# p1_apfc_and_standby.net
KiCad netlist of a schematic drawn in Altium Designer
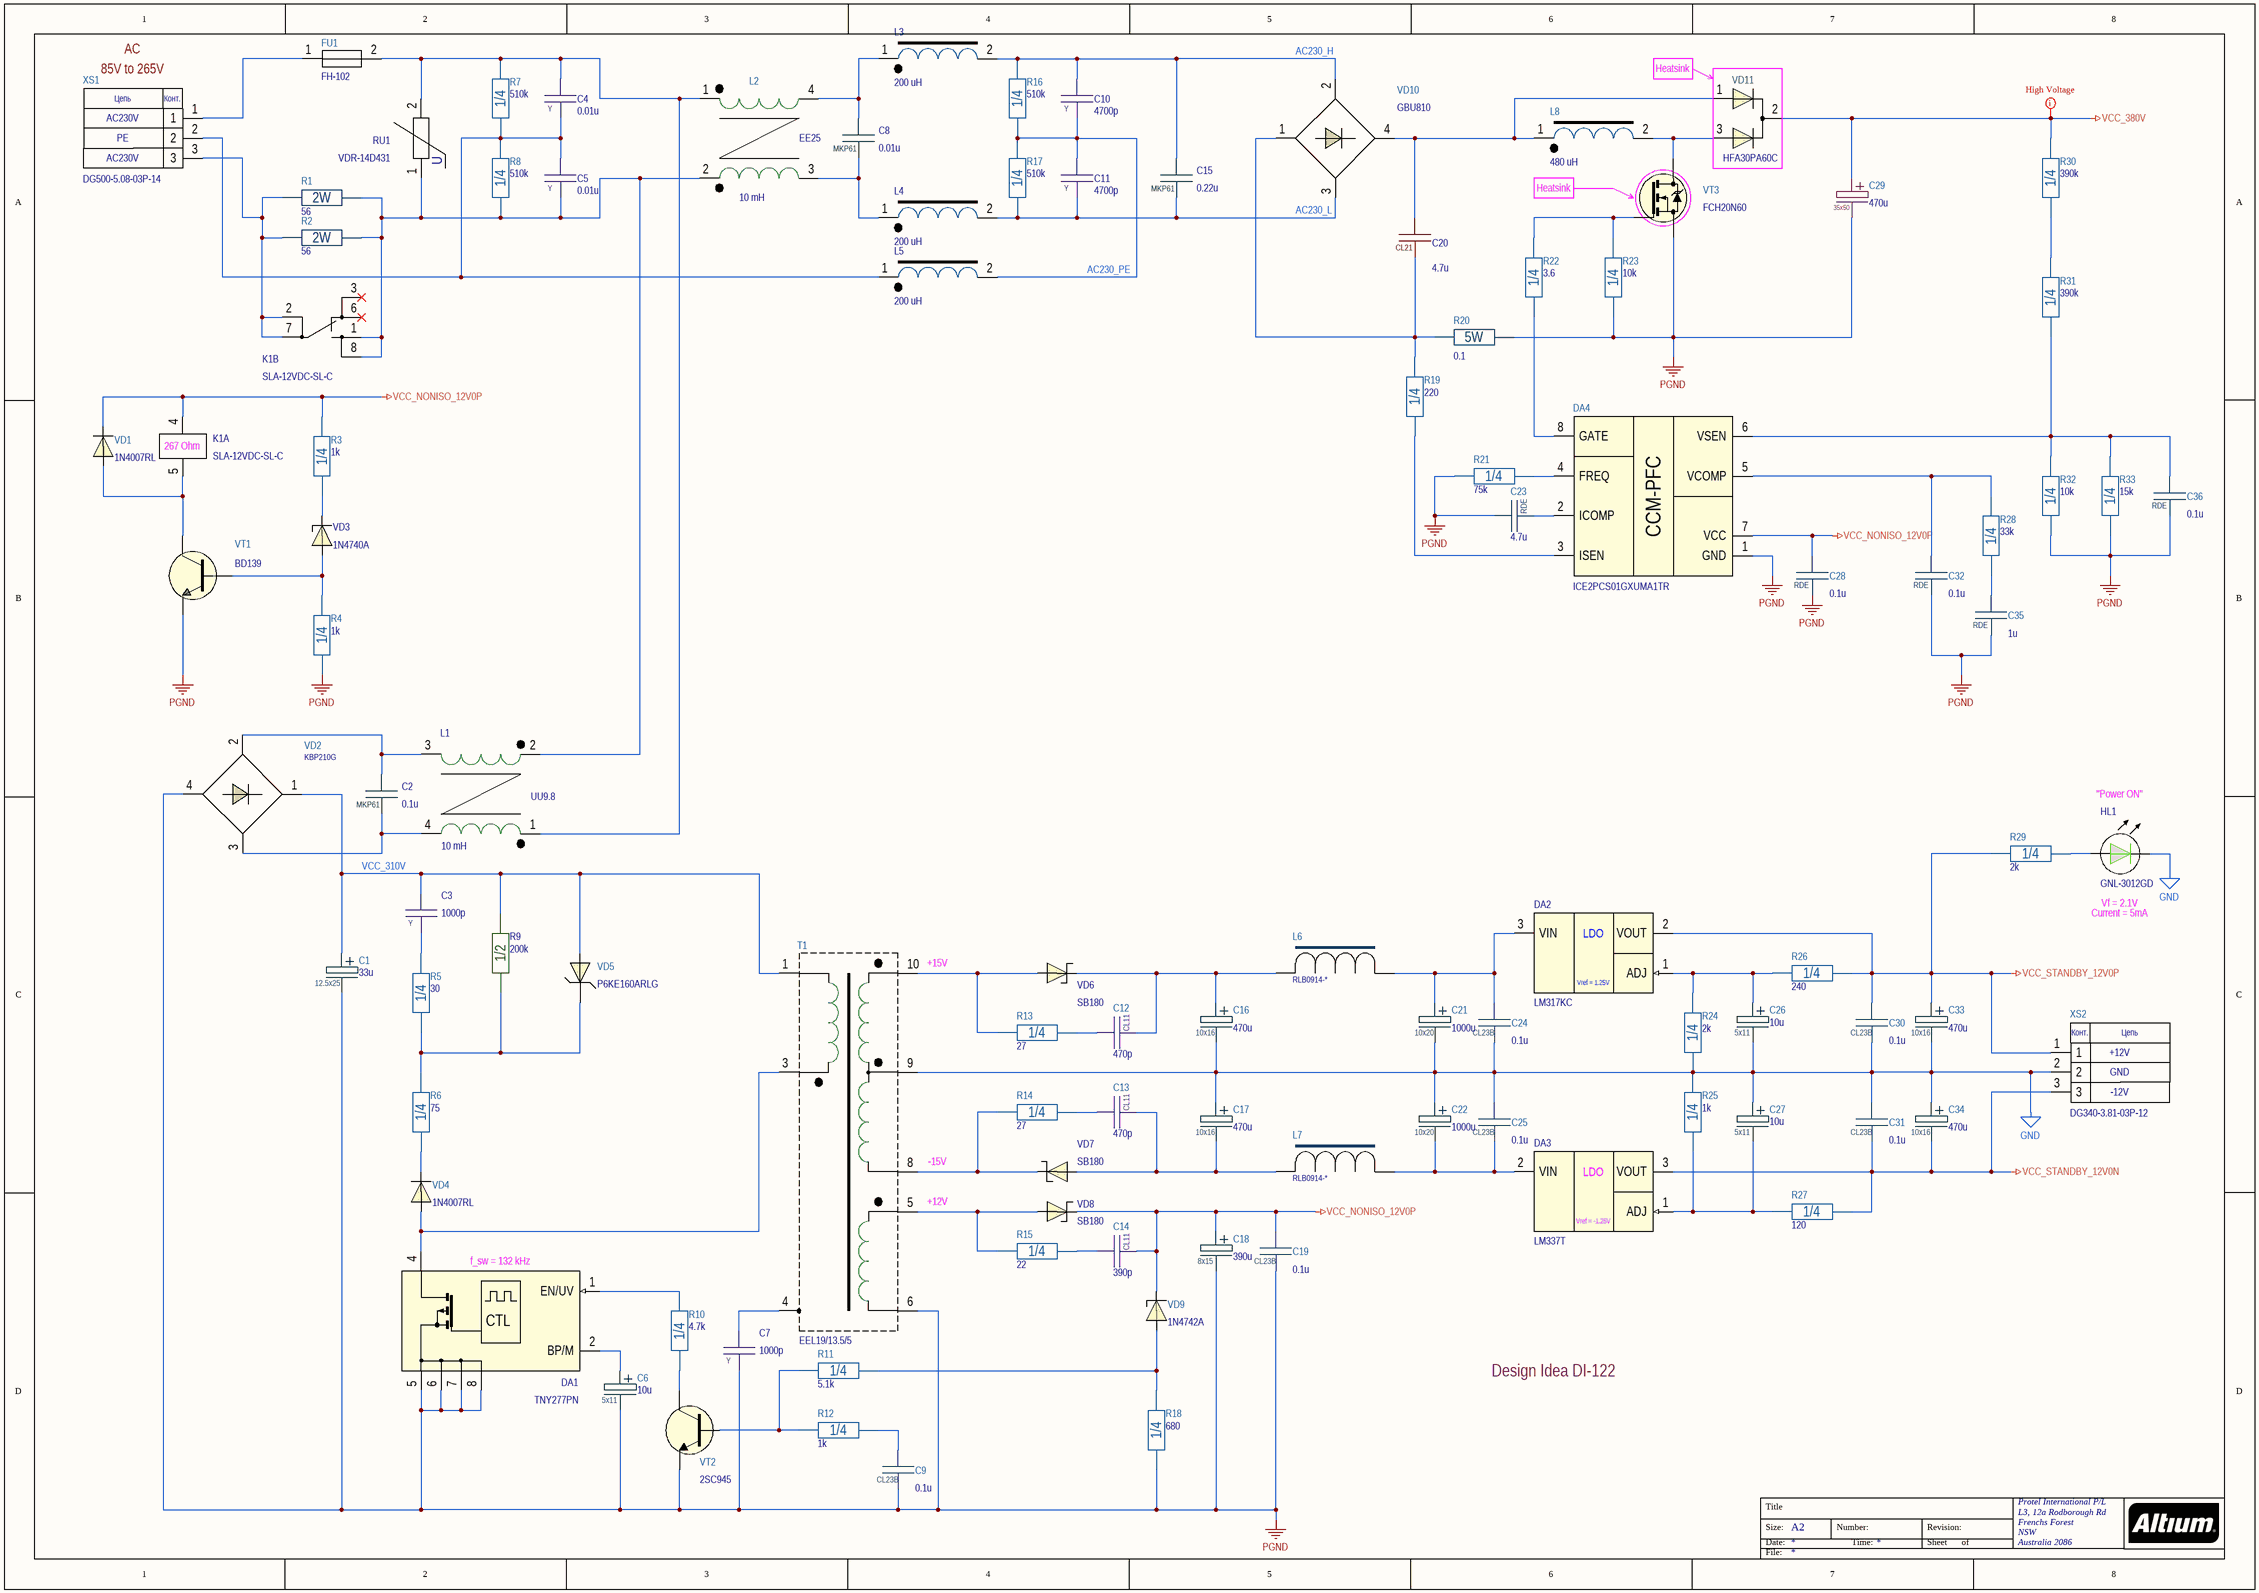
[diagram p0: p1_apfc_and_standby.SchDoc]

(export (version "E")
  (design (tool "Eeschema 10.0.6"))
  (components
    (comp (ref "C1")
      (value "33u")
      (footprint "PcbLib_RC:ECAP13X21X5_BRW")
      (description "Aluminium capacitor")
      (fields
        (field (name "TOLERANCE") "± 20 %")
        (field (name "VOLTAGE") "400V")
        (field (name "PACKAGE") "12.5x25")
      )
      (libsource (lib "Schlib_RC") (part "C_ECAP"))
    )
    (comp (ref "C2")
      (value "0.1u")
      (footprint "PcbLib_RC:MKP61_13x12x6_P10")
      (description "Metallized Polypropylene Film Capacitor for high voltage application")
      (fields
        (field (name "TOLERANCE") "± 10 %")
        (field (name "VOLTAGE") "300V")
        (field (name "PACKAGE") "MKP61")
      )
      (libsource (lib "Schlib_RC") (part "MKP61"))
    )
    (comp (ref "C3")
      (value "1000p")
      (footprint "PcbLib_RC:JYC_Y2_CAP_7.5")
      (description "High Voltage Ceramic Capacitor")
      (fields
        (field (name "TOLERANCE") "± 20 %")
        (field (name "VOLTAGE") "2000V")
        (field (name "PACKAGE") "Y")
      )
      (libsource (lib "Schlib_RC") (part "JB_Y2"))
    )
    (comp (ref "C4")
      (value "0.01u")
      (footprint "PcbLib_RC:JYC_Y2_CAP_6.5")
      (description "High Voltage Ceramic Capacitor")
      (fields
        (field (name "TOLERANCE") "± 20 %")
        (field (name "VOLTAGE") "2000V")
        (field (name "PACKAGE") "Y")
      )
      (libsource (lib "Schlib_RC") (part "JB_Y2"))
    )
    (comp (ref "C5")
      (value "0.01u")
      (footprint "PcbLib_RC:JYC_Y2_CAP_6.5")
      (description "High Voltage Ceramic Capacitor")
      (fields
        (field (name "TOLERANCE") "± 20 %")
        (field (name "VOLTAGE") "2000V")
        (field (name "PACKAGE") "Y")
      )
      (libsource (lib "Schlib_RC") (part "JB_Y2"))
    )
    (comp (ref "C6")
      (value "10u")
      (footprint "PcbLib_RC:ECAP5X11X2.0_BRW")
      (description "Aluminium capacitor")
      (fields
        (field (name "TOLERANCE") "± 20 %")
        (field (name "VOLTAGE") "63V")
        (field (name "PACKAGE") "5x11")
      )
      (libsource (lib "Schlib_RC") (part "C_ECAP"))
    )
    (comp (ref "C7")
      (value "1000p")
      (footprint "PcbLib_RC:JYC_Y2_CAP_7.5")
      (description "High Voltage Ceramic Capacitor")
      (fields
        (field (name "TOLERANCE") "± 20 %")
        (field (name "VOLTAGE") "2000V")
        (field (name "PACKAGE") "Y")
      )
      (libsource (lib "Schlib_RC") (part "JB_Y2"))
    )
    (comp (ref "C8")
      (value "0.01u")
      (footprint "PcbLib_RC:MKP61_18x12x6_P15")
      (description "Metallized Polypropylene Film Capacitor for high voltage application")
      (fields
        (field (name "TOLERANCE") "± 10 %")
        (field (name "VOLTAGE") "300V")
        (field (name "PACKAGE") "MKP61")
      )
      (libsource (lib "Schlib_RC") (part "MKP61"))
    )
    (comp (ref "C9")
      (value "0.1u")
      (footprint "PcbLib_RC:CL23B_7.2x2.5")
      (description "Box-type metallized polyester film capacitor")
      (fields
        (field (name "TOLERANCE") "± * %")
        (field (name "VOLTAGE") "63V")
        (field (name "PACKAGE") "CL23B")
      )
      (libsource (lib "Schlib_RC") (part "CL23B"))
    )
    (comp (ref "C10")
      (value "4700p")
      (footprint "PcbLib_RC:JYC_Y2_CAP_6.5")
      (description "High Voltage Ceramic Capacitor")
      (fields
        (field (name "TOLERANCE") "± 20 %")
        (field (name "VOLTAGE") "2000V")
        (field (name "PACKAGE") "Y")
      )
      (libsource (lib "Schlib_RC") (part "JB_Y2"))
    )
    (comp (ref "C11")
      (value "4700p")
      (footprint "PcbLib_RC:JYC_Y2_CAP_6.5")
      (description "High Voltage Ceramic Capacitor")
      (fields
        (field (name "TOLERANCE") "± 20 %")
        (field (name "VOLTAGE") "2000V")
        (field (name "PACKAGE") "Y")
      )
      (libsource (lib "Schlib_RC") (part "JB_Y2"))
    )
    (comp (ref "C12")
      (value "470p")
      (footprint "PcbLib_RC:CL11_6x4_P4.0")
      (description "CL11 Type Polyester Film Metal Foil Capacitor-inductive")
      (fields
        (field (name "TOLERANCE") "± 5 %")
        (field (name "VOLTAGE") "100V")
        (field (name "PACKAGE") "CL11")
      )
      (libsource (lib "Schlib_RC") (part "CL11"))
    )
    (comp (ref "C13")
      (value "470p")
      (footprint "PcbLib_RC:CL11_6x4_P4.0")
      (description "CL11 Type Polyester Film Metal Foil Capacitor-inductive")
      (fields
        (field (name "TOLERANCE") "± 5 %")
        (field (name "VOLTAGE") "100V")
        (field (name "PACKAGE") "CL11")
      )
      (libsource (lib "Schlib_RC") (part "CL11"))
    )
    (comp (ref "C14")
      (value "390p")
      (footprint "PcbLib_RC:CL11_6x4_P4.0")
      (description "CL11 Type Polyester Film Metal Foil Capacitor-inductive")
      (fields
        (field (name "TOLERANCE") "± 5 %")
        (field (name "VOLTAGE") "100V")
        (field (name "PACKAGE") "CL11")
      )
      (libsource (lib "Schlib_RC") (part "CL11"))
    )
    (comp (ref "C15")
      (value "0.22u")
      (footprint "PcbLib_RC:MKP61_18x14.5x8.5_P15")
      (description "Metallized Polypropylene Film Capacitor for high voltage application")
      (fields
        (field (name "TOLERANCE") "± 10 %")
        (field (name "VOLTAGE") "300V")
        (field (name "PACKAGE") "MKP61")
      )
      (libsource (lib "Schlib_RC") (part "MKP61"))
    )
    (comp (ref "C16")
      (value "470u")
      (footprint "PcbLib_RC:ECAP10X17X5_BRW")
      (description "Aluminium capacitor")
      (fields
        (field (name "TOLERANCE") "± 20 %")
        (field (name "VOLTAGE") "25V")
        (field (name "PACKAGE") "10x16")
      )
      (libsource (lib "Schlib_RC") (part "C_ECAP"))
    )
    (comp (ref "C17")
      (value "470u")
      (footprint "PcbLib_RC:ECAP10X17X5_BRW")
      (description "Aluminium capacitor")
      (fields
        (field (name "TOLERANCE") "± 20 %")
        (field (name "VOLTAGE") "25V")
        (field (name "PACKAGE") "10x16")
      )
      (libsource (lib "Schlib_RC") (part "C_ECAP"))
    )
    (comp (ref "C18")
      (value "390u")
      (footprint "PcbLib_RC:ECAP8X13.5X3.5_BRW")
      (description "Aluminium capacitor")
      (fields
        (field (name "TOLERANCE") "± 20 %")
        (field (name "VOLTAGE") "25V")
        (field (name "PACKAGE") "8x15")
      )
      (libsource (lib "Schlib_RC") (part "C_ECAP"))
    )
    (comp (ref "C19")
      (value "0.1u")
      (footprint "PcbLib_RC:CL23B_7.2x2.5")
      (description "Box-type metallized polyester film capacitor")
      (fields
        (field (name "TOLERANCE") "± * %")
        (field (name "VOLTAGE") "63V")
        (field (name "PACKAGE") "CL23B")
      )
      (libsource (lib "Schlib_RC") (part "CL23B"))
    )
    (comp (ref "C20")
      (value "4.7u")
      (footprint "PcbLib_RC:CL21_29x24.5x14.0_P27.5")
      (description "CL21 Type Metallized Polyester Film Capacitor")
      (fields
        (field (name "TOLERANCE") "± * %")
        (field (name "VOLTAGE") "630V")
        (field (name "PACKAGE") "CL21")
      )
      (libsource (lib "Schlib_RC") (part "CL21"))
    )
    (comp (ref "C21")
      (value "1000u")
      (footprint "PcbLib_RC:ECAP10X21X5_BRW")
      (description "Aluminium capacitor")
      (fields
        (field (name "TOLERANCE") "± 20 %")
        (field (name "VOLTAGE") "25V")
        (field (name "PACKAGE") "10x20")
      )
      (libsource (lib "Schlib_RC") (part "C_ECAP"))
    )
    (comp (ref "C22")
      (value "1000u")
      (footprint "PcbLib_RC:ECAP10X21X5_BRW")
      (description "Aluminium capacitor")
      (fields
        (field (name "TOLERANCE") "± 20 %")
        (field (name "VOLTAGE") "25V")
        (field (name "PACKAGE") "10x20")
      )
      (libsource (lib "Schlib_RC") (part "C_ECAP"))
    )
    (comp (ref "C23")
      (value "4.7u")
      (footprint "PcbLib_RC:RDE_2P1")
      (description "MLCC radial lead type with epoxy coat (RDE Series)")
      (fields
        (field (name "TOLERANCE") "± 10 %")
        (field (name "VOLTAGE") "50V")
        (field (name "PACKAGE") "RDE")
      )
      (libsource (lib "Schlib_RC") (part "RDE_CAP"))
    )
    (comp (ref "C24")
      (value "0.1u")
      (footprint "PcbLib_RC:CL23B_7.2x2.5")
      (description "Box-type metallized polyester film capacitor")
      (fields
        (field (name "TOLERANCE") "± * %")
        (field (name "VOLTAGE") "63V")
        (field (name "PACKAGE") "CL23B")
      )
      (libsource (lib "Schlib_RC") (part "CL23B"))
    )
    (comp (ref "C25")
      (value "0.1u")
      (footprint "PcbLib_RC:CL23B_7.2x2.5")
      (description "Box-type metallized polyester film capacitor")
      (fields
        (field (name "TOLERANCE") "± * %")
        (field (name "VOLTAGE") "63V")
        (field (name "PACKAGE") "CL23B")
      )
      (libsource (lib "Schlib_RC") (part "CL23B"))
    )
    (comp (ref "C26")
      (value "10u")
      (footprint "PcbLib_RC:ECAP5X11X2.0_BRW")
      (description "Aluminium capacitor")
      (fields
        (field (name "TOLERANCE") "± 20 %")
        (field (name "VOLTAGE") "63V")
        (field (name "PACKAGE") "5x11")
      )
      (libsource (lib "Schlib_RC") (part "C_ECAP"))
    )
    (comp (ref "C27")
      (value "10u")
      (footprint "PcbLib_RC:ECAP5X11X2.0_BRW")
      (description "Aluminium capacitor")
      (fields
        (field (name "TOLERANCE") "± 20 %")
        (field (name "VOLTAGE") "63V")
        (field (name "PACKAGE") "5x11")
      )
      (libsource (lib "Schlib_RC") (part "C_ECAP"))
    )
    (comp (ref "C28")
      (value "0.1u")
      (footprint "PcbLib_RC:RDE_1P1")
      (description "MLCC radial lead type with epoxy coat (RDE Series)")
      (fields
        (field (name "TOLERANCE") "± 10 %")
        (field (name "VOLTAGE") "100V")
        (field (name "PACKAGE") "RDE")
      )
      (libsource (lib "Schlib_RC") (part "RDE_CAP"))
    )
    (comp (ref "C29")
      (value "470u")
      (footprint "PcbLib_RC:ECAP35X50X10")
      (description "Aluminium capacitors 35x50mm")
      (fields
        (field (name "TOLERANCE") "± 20 %")
        (field (name "VOLTAGE") "450V")
        (field (name "PACKAGE") "35x50")
      )
      (libsource (lib "Schlib_RC") (part "ECAP_35x50"))
    )
    (comp (ref "C30")
      (value "0.1u")
      (footprint "PcbLib_RC:CL23B_7.2x2.5")
      (description "Box-type metallized polyester film capacitor")
      (fields
        (field (name "TOLERANCE") "± * %")
        (field (name "VOLTAGE") "63V")
        (field (name "PACKAGE") "CL23B")
      )
      (libsource (lib "Schlib_RC") (part "CL23B"))
    )
    (comp (ref "C31")
      (value "0.1u")
      (footprint "PcbLib_RC:CL23B_7.2x2.5")
      (description "Box-type metallized polyester film capacitor")
      (fields
        (field (name "TOLERANCE") "± * %")
        (field (name "VOLTAGE") "63V")
        (field (name "PACKAGE") "CL23B")
      )
      (libsource (lib "Schlib_RC") (part "CL23B"))
    )
    (comp (ref "C32")
      (value "0.1u")
      (footprint "PcbLib_RC:RDE_1P1")
      (description "MLCC radial lead type with epoxy coat (RDE Series)")
      (fields
        (field (name "TOLERANCE") "± 10 %")
        (field (name "VOLTAGE") "100V")
        (field (name "PACKAGE") "RDE")
      )
      (libsource (lib "Schlib_RC") (part "RDE_CAP"))
    )
    (comp (ref "C33")
      (value "470u")
      (footprint "PcbLib_RC:ECAP10X17X5_BRW")
      (description "Aluminium capacitor")
      (fields
        (field (name "TOLERANCE") "± 20 %")
        (field (name "VOLTAGE") "25V")
        (field (name "PACKAGE") "10x16")
      )
      (libsource (lib "Schlib_RC") (part "C_ECAP"))
    )
    (comp (ref "C34")
      (value "470u")
      (footprint "PcbLib_RC:ECAP10X17X5_BRW")
      (description "Aluminium capacitor")
      (fields
        (field (name "TOLERANCE") "± 20 %")
        (field (name "VOLTAGE") "25V")
        (field (name "PACKAGE") "10x16")
      )
      (libsource (lib "Schlib_RC") (part "C_ECAP"))
    )
    (comp (ref "C35")
      (value "1u")
      (footprint "PcbLib_RC:RDE_2P1")
      (description "MLCC radial lead type with epoxy coat (RDE Series)")
      (fields
        (field (name "TOLERANCE") "± 10 %")
        (field (name "VOLTAGE") "50V")
        (field (name "PACKAGE") "RDE")
      )
      (libsource (lib "Schlib_RC") (part "RDE_CAP"))
    )
    (comp (ref "C36")
      (value "0.1u")
      (footprint "PcbLib_RC:RDE_1P1")
      (description "MLCC radial lead type with epoxy coat (RDE Series)")
      (fields
        (field (name "TOLERANCE") "± 10 %")
        (field (name "VOLTAGE") "100V")
        (field (name "PACKAGE") "RDE")
      )
      (libsource (lib "Schlib_RC") (part "RDE_CAP"))
    )
    (comp (ref "DA1")
      (value "TNY277PN")
      (footprint "PcbLib_ICs:DIP-8C")
      (description "Energy-Effi cient, Off-Line Switcher With Enhanced Flexibility and Extended Power Range")
      (fields (field (name "MANUFACTURER") "Power Integrations"))
      (libsource (lib "Schlib_OtherComponents") (part "TNY277PN"))
    )
    (comp (ref "DA2")
      (value "LM317KC")
      (footprint "PcbLib_ICs:TO-220A-3")
      (description "1.5 A 3-Terminal Adjustable Regulator")
      (fields (field (name "MANUFACTURER") "Texas Instruments"))
      (libsource (lib "Schlib_Texas_Instruments") (part "LM317KC"))
    )
    (comp (ref "DA3")
      (value "LM337T")
      (footprint "PcbLib_ICs:TO-220A-3")
      (description "-1.5A  3-Terminal Adjustable Negative Regulators")
      (fields (field (name "MANUFACTURER") "Texas Instruments"))
      (libsource (lib "Schlib_Texas_Instruments") (part "LM337T"))
    )
    (comp (ref "DA4")
      (value "ICE2PCS01GXUMA1TR")
      (footprint "PcbLib_ICs:SOIC-8_with_DIP-8")
      (description "PFC Controller in Continuous Conduction Mode")
      (fields (field (name "MANUFACTURER") "Infineon"))
      (libsource (lib "Schlib_Infineon") (part "ICE2PCS01GXUMA1TR"))
    )
    (comp (ref "FU1")
      (value "FH-102")
      (footprint "PcbLib_Others:FH-102")
      (description "Fuse holder 5.2х20mm")
      (libsource (lib "Schlib_OtherComponents") (part "FH-102"))
    )
    (comp (ref "HL1")
      (value "GNL-3012GD")
      (footprint "PcbLib_Discrete:GNL-3012GD")
      (description "Standard Brightness 3mm LED")
      (fields (field (name "MANUFACTURER") "G-Nor Optoelectronics"))
      (libsource (lib "Schlib_OtherComponents") (part "GNL-3012GD"))
    )
    (comp (ref "K1")
      (value "SLA-12VDC-SL-C")
      (footprint "PcbLib_Others:RELAY_13x29.5MM")
      (description "Subminature high power relay 16A")
      (fields (field (name "MANUFACTURER") "Songle Relay"))
      (libsource (lib "") (part "SMIH-12VDC-SL-C_1"))
    )
    (comp (ref "L1")
      (value "10 mH")
      (footprint "PcbLib_Others:UU9.8")
      (description "UU9.8 Ferrite Core inductor")
      (fields (field (name "CORE") "UU9.8"))
      (libsource (lib "Schlib_OtherComponents") (part "UU9.8"))
    )
    (comp (ref "L2")
      (value "10 mH")
      (footprint "PcbLib_Others:EE25/10/6")
      (description "EE25 Ferrite Core inductor")
      (fields (field (name "CORE") "EE25"))
      (libsource (lib "Schlib_OtherComponents") (part "EE25"))
    )
    (comp (ref "L3")
      (value "200 uH")
      (footprint "PcbLib_RC:CORE_D20_GB")
      (description "Ferrite Core D20.3/12.7/6.35 mm")
      (libsource (lib "Schlib_OtherComponents") (part "CORE_D20"))
    )
    (comp (ref "L4")
      (value "200 uH")
      (footprint "PcbLib_RC:CORE_D20_GB")
      (description "Ferrite Core D20.3/12.7/6.35 mm")
      (libsource (lib "Schlib_OtherComponents") (part "CORE_D20"))
    )
    (comp (ref "L5")
      (value "200 uH")
      (footprint "PcbLib_RC:CORE_D20_YW")
      (description "Ferrite Core D20.3/12.7/6.35 mm")
      (libsource (lib "Schlib_OtherComponents") (part "CORE_D20"))
    )
    (comp (ref "L6")
      (value "RLB0914-*")
      (footprint "PcbLib_RC:RLB0914")
      (description "Radial Inductors")
      (fields (field (name "MANUFACTURER") "Bourns Inc."))
      (libsource (lib "Schlib_Bourns") (part "RLB0914"))
    )
    (comp (ref "L7")
      (value "RLB0914-*")
      (footprint "PcbLib_RC:RLB0914")
      (description "Radial Inductors")
      (fields (field (name "MANUFACTURER") "Bourns Inc."))
      (libsource (lib "Schlib_Bourns") (part "RLB0914"))
    )
    (comp (ref "L8")
      (value "480 uH")
      (footprint "PcbLib_RC:CORE_D36_GB")
      (description "Ferrite Core D35.8/22.4/10.5 mm")
      (libsource (lib "Schlib_OtherComponents") (part "CORE_D36"))
    )
    (comp (ref "R1")
      (value "56")
      (footprint "PcbLib_RC:CFR-200(VERTICAL)")
      (description "Resistor 2W")
      (fields
        (field (name "TOLERANCE") "± 5 %")
        (field (name "PART NUMBER") "KNP200JB-73-56R")
        (field (name "PACKAGE") "2W")
      )
      (libsource (lib "Schlib_RC") (part "CF200"))
    )
    (comp (ref "R2")
      (value "56")
      (footprint "PcbLib_RC:CFR-200(VERTICAL)")
      (description "Resistor 2W")
      (fields
        (field (name "TOLERANCE") "± 5 %")
        (field (name "PART NUMBER") "KNP200JB-73-56R")
        (field (name "PACKAGE") "2W")
      )
      (libsource (lib "Schlib_RC") (part "CF200"))
    )
    (comp (ref "R3")
      (value "1k")
      (footprint "PcbLib_RC:CFR-25")
      (description "Resistor 1/4W")
      (fields
        (field (name "TOLERANCE") "± 1 %")
        (field (name "PART NUMBER") "MFR-25FTF52-1K")
        (field (name "PACKAGE") "1/4")
      )
      (libsource (lib "Schlib_RC") (part "CF25"))
    )
    (comp (ref "R4")
      (value "1k")
      (footprint "PcbLib_RC:CFR-25")
      (description "Resistor 1/4W")
      (fields
        (field (name "TOLERANCE") "± 1 %")
        (field (name "PART NUMBER") "MFR-25FTF52-1K")
        (field (name "PACKAGE") "1/4")
      )
      (libsource (lib "Schlib_RC") (part "CF25"))
    )
    (comp (ref "R5")
      (value "30")
      (footprint "PcbLib_RC:CFR-25")
      (description "Resistor 1/4W")
      (fields
        (field (name "TOLERANCE") "± 1 %")
        (field (name "PART NUMBER") "MFR-25FTF52-30R")
        (field (name "PACKAGE") "1/4")
      )
      (libsource (lib "Schlib_RC") (part "CF25"))
    )
    (comp (ref "R6")
      (value "75")
      (footprint "PcbLib_RC:CFR-25(VERTICAL)")
      (description "Resistor 1/4W")
      (fields
        (field (name "TOLERANCE") "± 1 %")
        (field (name "PART NUMBER") "MFR-25FTF52-75R")
        (field (name "PACKAGE") "1/4")
      )
      (libsource (lib "Schlib_RC") (part "CF25"))
    )
    (comp (ref "R7")
      (value "510k")
      (footprint "PcbLib_RC:CFR-25")
      (description "Resistor 1/4W")
      (fields
        (field (name "TOLERANCE") "± 1 %")
        (field (name "PART NUMBER") "MFR-25FTF52-510K")
        (field (name "PACKAGE") "1/4")
      )
      (libsource (lib "Schlib_RC") (part "CF25"))
    )
    (comp (ref "R8")
      (value "510k")
      (footprint "PcbLib_RC:CFR-25")
      (description "Resistor 1/4W")
      (fields
        (field (name "TOLERANCE") "± 1 %")
        (field (name "PART NUMBER") "MFR-25FTF52-510K")
        (field (name "PACKAGE") "1/4")
      )
      (libsource (lib "Schlib_RC") (part "CF25"))
    )
    (comp (ref "R9")
      (value "200k")
      (footprint "PcbLib_RC:CFR-50")
      (description "Resistor 1/2W")
      (fields
        (field (name "TOLERANCE") "± 5 %")
        (field (name "PART NUMBER") "MFR-50JT-52-200K")
        (field (name "PACKAGE") "1/2")
      )
      (libsource (lib "Schlib_RC") (part "CF50"))
    )
    (comp (ref "R10")
      (value "4.7k")
      (footprint "PcbLib_RC:CFR-25(VERTICAL)")
      (description "Resistor 1/4W")
      (fields
        (field (name "TOLERANCE") "± 1 %")
        (field (name "PART NUMBER") "MFR-25FTF52-4K7")
        (field (name "PACKAGE") "1/4")
      )
      (libsource (lib "Schlib_RC") (part "CF25"))
    )
    (comp (ref "R11")
      (value "5.1k")
      (footprint "PcbLib_RC:CFR-25(VERTICAL)")
      (description "Resistor 1/4W")
      (fields
        (field (name "TOLERANCE") "± 1 %")
        (field (name "PART NUMBER") "MFR-25FTF52-5K1")
        (field (name "PACKAGE") "1/4")
      )
      (libsource (lib "Schlib_RC") (part "CF25"))
    )
    (comp (ref "R12")
      (value "1k")
      (footprint "PcbLib_RC:CFR-25")
      (description "Resistor 1/4W")
      (fields
        (field (name "TOLERANCE") "± 1 %")
        (field (name "PART NUMBER") "MFR-25FTF52-1K")
        (field (name "PACKAGE") "1/4")
      )
      (libsource (lib "Schlib_RC") (part "CF25"))
    )
    (comp (ref "R13")
      (value "27")
      (footprint "PcbLib_RC:CFR-25(VERTICAL)")
      (description "Resistor 1/4W")
      (fields
        (field (name "TOLERANCE") "± 1 %")
        (field (name "PART NUMBER") "MFR-25FTF52-27R")
        (field (name "PACKAGE") "1/4")
      )
      (libsource (lib "Schlib_RC") (part "CF25"))
    )
    (comp (ref "R14")
      (value "27")
      (footprint "PcbLib_RC:CFR-25(VERTICAL)")
      (description "Resistor 1/4W")
      (fields
        (field (name "TOLERANCE") "± 1 %")
        (field (name "PART NUMBER") "MFR-25FTF52-27R")
        (field (name "PACKAGE") "1/4")
      )
      (libsource (lib "Schlib_RC") (part "CF25"))
    )
    (comp (ref "R15")
      (value "22")
      (footprint "PcbLib_RC:CFR-25(VERTICAL)")
      (description "Resistor 1/4W")
      (fields
        (field (name "TOLERANCE") "± 1 %")
        (field (name "PART NUMBER") "MFR-25FTF52-22R")
        (field (name "PACKAGE") "1/4")
      )
      (libsource (lib "Schlib_RC") (part "CF25"))
    )
    (comp (ref "R16")
      (value "510k")
      (footprint "PcbLib_RC:CFR-25")
      (description "Resistor 1/4W")
      (fields
        (field (name "TOLERANCE") "± 1 %")
        (field (name "PART NUMBER") "MFR-25FTF52-510K")
        (field (name "PACKAGE") "1/4")
      )
      (libsource (lib "Schlib_RC") (part "CF25"))
    )
    (comp (ref "R17")
      (value "510k")
      (footprint "PcbLib_RC:CFR-25")
      (description "Resistor 1/4W")
      (fields
        (field (name "TOLERANCE") "± 1 %")
        (field (name "PART NUMBER") "MFR-25FTF52-510K")
        (field (name "PACKAGE") "1/4")
      )
      (libsource (lib "Schlib_RC") (part "CF25"))
    )
    (comp (ref "R18")
      (value "680")
      (footprint "PcbLib_RC:CFR-25")
      (description "Resistor 1/4W")
      (fields
        (field (name "TOLERANCE") "± 1 %")
        (field (name "PART NUMBER") "MFR-25FTF52-680R")
        (field (name "PACKAGE") "1/4")
      )
      (libsource (lib "Schlib_RC") (part "CF25"))
    )
    (comp (ref "R19")
      (value "220")
      (footprint "PcbLib_RC:CFR-25(VERTICAL)")
      (description "Resistor 1/4W")
      (fields
        (field (name "TOLERANCE") "± 1 %")
        (field (name "PART NUMBER") "MFR-25FTF52-220R")
        (field (name "PACKAGE") "1/4")
      )
      (libsource (lib "Schlib_RC") (part "CF25"))
    )
    (comp (ref "R20")
      (value "0.1")
      (footprint "PcbLib_RC:BPR58")
      (description "Rectangular type metal plate resistors")
      (fields
        (field (name "TOLERANCE") "± 5 %")
        (field (name "PART NUMBER") "BPR58CR10J")
        (field (name "PACKAGE") "5W")
      )
      (libsource (lib "Schlib_RC") (part "BPR58"))
    )
    (comp (ref "R21")
      (value "75k")
      (footprint "PcbLib_RC:CFR-25")
      (description "Resistor 1/4W")
      (fields
        (field (name "TOLERANCE") "± 1 %")
        (field (name "PART NUMBER") "MFR-25FTF52-75K")
        (field (name "PACKAGE") "1/4")
      )
      (libsource (lib "Schlib_RC") (part "CF25"))
    )
    (comp (ref "R22")
      (value "3.6")
      (footprint "PcbLib_RC:CFR-25(VERTICAL)")
      (description "Resistor 1/4W")
      (fields
        (field (name "TOLERANCE") "± 1 %")
        (field (name "PART NUMBER") "MFR-25FTF52-3R6")
        (field (name "PACKAGE") "1/4")
      )
      (libsource (lib "Schlib_RC") (part "CF25"))
    )
    (comp (ref "R23")
      (value "10k")
      (footprint "PcbLib_RC:CFR-25")
      (description "Resistor 1/4W")
      (fields
        (field (name "TOLERANCE") "± 1 %")
        (field (name "PART NUMBER") "MFR-25FTF52-10K")
        (field (name "PACKAGE") "1/4")
      )
      (libsource (lib "Schlib_RC") (part "CF25"))
    )
    (comp (ref "R24")
      (value "2k")
      (footprint "PcbLib_RC:CFR-25(VERTICAL)")
      (description "Resistor 1/4W")
      (fields
        (field (name "TOLERANCE") "± 1 %")
        (field (name "PART NUMBER") "MFR-25FTF52-2K")
        (field (name "PACKAGE") "1/4")
      )
      (libsource (lib "Schlib_RC") (part "CF25"))
    )
    (comp (ref "R25")
      (value "1k")
      (footprint "PcbLib_RC:CFR-25(VERTICAL)")
      (description "Resistor 1/4W")
      (fields
        (field (name "TOLERANCE") "± 1 %")
        (field (name "PART NUMBER") "MFR-25FTF52-1K")
        (field (name "PACKAGE") "1/4")
      )
      (libsource (lib "Schlib_RC") (part "CF25"))
    )
    (comp (ref "R26")
      (value "240")
      (footprint "PcbLib_RC:CFR-25(VERTICAL)")
      (description "Resistor 1/4W")
      (fields
        (field (name "TOLERANCE") "± 1 %")
        (field (name "PART NUMBER") "MFR-25FTF52-240R")
        (field (name "PACKAGE") "1/4")
      )
      (libsource (lib "Schlib_RC") (part "CF25"))
    )
    (comp (ref "R27")
      (value "120")
      (footprint "PcbLib_RC:CFR-25(VERTICAL)")
      (description "Resistor 1/4W")
      (fields
        (field (name "TOLERANCE") "± 1 %")
        (field (name "PART NUMBER") "MFR-25FTF52-120R")
        (field (name "PACKAGE") "1/4")
      )
      (libsource (lib "Schlib_RC") (part "CF25"))
    )
    (comp (ref "R28")
      (value "33k")
      (footprint "PcbLib_RC:CFR-25(VERTICAL)")
      (description "Resistor 1/4W")
      (fields
        (field (name "TOLERANCE") "± 1 %")
        (field (name "PART NUMBER") "MFR-25FTF52-33K")
        (field (name "PACKAGE") "1/4")
      )
      (libsource (lib "Schlib_RC") (part "CF25"))
    )
    (comp (ref "R29")
      (value "2k")
      (footprint "PcbLib_RC:CFR-25(VERTICAL)")
      (description "Resistor 1/4W")
      (fields
        (field (name "TOLERANCE") "± 1 %")
        (field (name "PART NUMBER") "MFR-25FTF52-2K")
        (field (name "PACKAGE") "1/4")
      )
      (libsource (lib "Schlib_RC") (part "CF25"))
    )
    (comp (ref "R30")
      (value "390k")
      (footprint "PcbLib_RC:CFR-25(VERTICAL)")
      (description "Resistor 1/4W")
      (fields
        (field (name "TOLERANCE") "± 1 %")
        (field (name "PART NUMBER") "MFR-25FTF52-390K")
        (field (name "PACKAGE") "1/4")
      )
      (libsource (lib "Schlib_RC") (part "CF25"))
    )
    (comp (ref "R31")
      (value "390k")
      (footprint "PcbLib_RC:CFR-25(VERTICAL)")
      (description "Resistor 1/4W")
      (fields
        (field (name "TOLERANCE") "± 1 %")
        (field (name "PART NUMBER") "MFR-25FTF52-390K")
        (field (name "PACKAGE") "1/4")
      )
      (libsource (lib "Schlib_RC") (part "CF25"))
    )
    (comp (ref "R32")
      (value "10k")
      (footprint "PcbLib_RC:CFR-25(VERTICAL)")
      (description "Resistor 1/4W")
      (fields
        (field (name "TOLERANCE") "± 1 %")
        (field (name "PART NUMBER") "MFR-25FTF52-10K")
        (field (name "PACKAGE") "1/4")
      )
      (libsource (lib "Schlib_RC") (part "CF25"))
    )
    (comp (ref "R33")
      (value "15k")
      (footprint "PcbLib_RC:CFR-25(VERTICAL)")
      (description "Resistor 1/4W")
      (fields
        (field (name "TOLERANCE") "± 1 %")
        (field (name "PART NUMBER") "MFR-25FTF52-15K")
        (field (name "PACKAGE") "1/4")
      )
      (libsource (lib "Schlib_RC") (part "CF25"))
    )
    (comp (ref "RU1")
      (value "VDR-14D431")
      (footprint "PcbLib_Others:VARISTOR_14D")
      (description "Varistor")
      (libsource (lib "Schlib_OtherComponents") (part "VARISTOR"))
    )
    (comp (ref "T1")
      (value "EEL19/13.5/5")
      (footprint "PcbLib_Others:EEL19/13.5/5")
      (description "EEL19 Ferrite Core, 2 output")
      (libsource (lib "Schlib_OtherComponents") (part "EEL19_V1"))
    )
    (comp (ref "VD1")
      (value "1N4007RL")
      (footprint "PcbLib_Discrete:DO-41")
      (description "1A 1000V Standard Recovery Rectifiers Diode")
      (fields (field (name "MANUFACTURER") "ON Semiconductor"))
      (libsource (lib "Schlib_ONSemiconductor") (part "1N4007RL"))
    )
    (comp (ref "VD2")
      (value "KBP210G")
      (footprint "PcbLib_Discrete:KBP210G")
      (description "2A single phase bridge rectifier")
      (fields (field (name "MANUFACTURER") "Diodes Incorporated"))
      (libsource (lib "Schlib_OtherComponents") (part "KBP210G"))
    )
    (comp (ref "VD3")
      (value "1N4740A")
      (footprint "PcbLib_Discrete:DO-41 GLASS DARK RED")
      (description "10V 1.0W ZENER DIODE")
      (fields (field (name "MANUFACTURER") "Diodes Incorporated"))
      (libsource (lib "Schlib_Diodes_Incorporated") (part "1N4740A"))
    )
    (comp (ref "VD4")
      (value "1N4007RL")
      (footprint "PcbLib_Discrete:DO-41")
      (description "1A 1000V Standard Recovery Rectifiers Diode")
      (fields (field (name "MANUFACTURER") "ON Semiconductor"))
      (libsource (lib "Schlib_ONSemiconductor") (part "1N4007RL"))
    )
    (comp (ref "VD5")
      (value "P6KE160ARLG")
      (footprint "PcbLib_Discrete:DO-15")
      (description "600 Watt Peak Power Transient\r\nVoltage Suppressors")
      (fields (field (name "MANUFACTURER") "ON Semiconductor"))
      (libsource (lib "Schlib_ONSemiconductor") (part "P6KE160ARLG"))
    )
    (comp (ref "VD6")
      (value "SB180")
      (footprint "PcbLib_Discrete:DO-41")
      (description "1A, 80V Schottky Barrier Rectifier")
      (fields (field (name "MANUFACTURER") "ON Semiconductor"))
      (libsource (lib "Schlib_ONSemiconductor") (part "SB180"))
    )
    (comp (ref "VD7")
      (value "SB180")
      (footprint "PcbLib_Discrete:DO-41")
      (description "1A, 80V Schottky Barrier Rectifier")
      (fields (field (name "MANUFACTURER") "ON Semiconductor"))
      (libsource (lib "Schlib_ONSemiconductor") (part "SB180"))
    )
    (comp (ref "VD8")
      (value "SB180")
      (footprint "PcbLib_Discrete:DO-41")
      (description "1A, 80V Schottky Barrier Rectifier")
      (fields (field (name "MANUFACTURER") "ON Semiconductor"))
      (libsource (lib "Schlib_ONSemiconductor") (part "SB180"))
    )
    (comp (ref "VD9")
      (value "1N4742A")
      (footprint "PcbLib_Discrete:DO-41 GLASS DARK RED")
      (description "12V 1.0W ZENER DIODE")
      (fields (field (name "MANUFACTURER") "Diodes Incorporated"))
      (libsource (lib "Schlib_Diodes_Incorporated") (part "1N4742A"))
    )
    (comp (ref "VD10")
      (value "GBU810")
      (footprint "PcbLib_Discrete:GBU810")
      (description "8A single phase bridge rectifier")
      (fields (field (name "MANUFACTURER") "Diodes Incorporated"))
      (libsource (lib "Schlib_OtherComponents") (part "GBU810"))
    )
    (comp (ref "VD11")
      (value "HFA30PA60C")
      (footprint "PcbLib_ICs:TO-247_with_dual_TO-220")
      (description "Ultrafast, Soft Recovery Diode 600V, 15A")
      (fields (field (name "MANUFACTURER") "Infineon"))
      (libsource (lib "Schlib_Infineon") (part "HFA30PA60C"))
    )
    (comp (ref "VT1")
      (value "BD139")
      (footprint "PcbLib_ICs:TO-126 (VERTICAL)")
      (description "General Purpose n-p-n Transistors")
      (fields (field (name "MANUFACTURER") "STMicroelectronics"))
      (libsource (lib "Schlib_STMicroelectronics") (part "BD139"))
    )
    (comp (ref "VT2")
      (value "2SC945")
      (footprint "PcbLib_ICs:TO-92 (VERTICAL,LINE)")
      (description "General Purpose n-p-n Transistors")
      (fields (field (name "MANUFACTURER") "NEC"))
      (libsource (lib "Schlib_NEC") (part "2SC945"))
    )
    (comp (ref "VT3")
      (value "FCH20N60")
      (footprint "PcbLib_ICs:TO-247_with_TO-220 (VERTICAL)")
      (description "600V @ 20A N-Channel MOSFET")
      (fields (field (name "MANUFACTURER") "ON Semiconductor"))
      (libsource (lib "Schlib_ONSemiconductor") (part "FCH20N60"))
    )
    (comp (ref "XS1")
      (value "DG500-5.08-03P-14")
      (footprint "PcbLib_Connectors:DG500-5.08-03P")
      (description "3-way screw terminal, pitch 200mils (5.08mm)")
      (fields (field (name "MANUFACTURER") "DEGSON"))
      (libsource (lib "Schlib_OtherComponents") (part "DG500-5.08-03P-14"))
    )
    (comp (ref "XS2")
      (value "DG340-3.81-03P-12")
      (footprint "PcbLib_Connectors:DG340-3.81-03P")
      (description "3-way screw terminal, pitch 150mils (3.81mm)")
      (fields (field (name "MANUFACTURER") "DEGSON"))
      (libsource (lib "Schlib_OtherComponents") (part "DG340-3.81-03P-12"))
    )
  )
  (nets
    (net (code "1") (name "/AC230_H") (class "Default")
      (node (ref "C10") (pin "1") (pinfunction "1_1") (pintype "passive"))
      (node (ref "C15") (pin "2") (pinfunction "2_2") (pintype "passive"))
      (node (ref "L3") (pin "2") (pinfunction "2_2") (pintype "passive"))
      (node (ref "R16") (pin "2") (pinfunction "2_2") (pintype "passive"))
      (node (ref "VD10") (pin "2") (pinfunction "AC1_2") (pintype "passive"))
    )
    (net (code "2") (name "/AC230_L") (class "Default")
      (node (ref "C11") (pin "2") (pinfunction "2_2") (pintype "passive"))
      (node (ref "C15") (pin "1") (pinfunction "1_1") (pintype "passive"))
      (node (ref "L4") (pin "2") (pinfunction "2_2") (pintype "passive"))
      (node (ref "R17") (pin "1") (pinfunction "1_1") (pintype "passive"))
      (node (ref "VD10") (pin "3") (pinfunction "AC2_3") (pintype "passive"))
    )
    (net (code "3") (name "/AC230_PE") (class "Default")
      (node (ref "C10") (pin "2") (pinfunction "2_2") (pintype "passive"))
      (node (ref "C11") (pin "1") (pinfunction "1_1") (pintype "passive"))
      (node (ref "L5") (pin "2") (pinfunction "2_2") (pintype "passive"))
      (node (ref "R16") (pin "1") (pinfunction "1_1") (pintype "passive"))
      (node (ref "R17") (pin "2") (pinfunction "2_2") (pintype "passive"))
    )
    (net (code "4") (name "/VCC_310V") (class "Default")
      (node (ref "C1") (pin "1") (pinfunction "1_1") (pintype "passive"))
      (node (ref "C3") (pin "2") (pinfunction "2_2") (pintype "passive"))
      (node (ref "R9") (pin "2") (pinfunction "2_2") (pintype "passive"))
      (node (ref "T1") (pin "1") (pinfunction "1_1") (pintype "passive"))
      (node (ref "VD2") (pin "1") (pinfunction "M_1") (pintype "passive"))
      (node (ref "VD5") (pin "2") (pinfunction "A_2") (pintype "passive"))
    )
    (net (code "5") (name "GND") (class "Default")
      (node (ref "C16") (pin "2") (pinfunction "2_2") (pintype "passive"))
      (node (ref "C17") (pin "1") (pinfunction "1_1") (pintype "passive"))
      (node (ref "C21") (pin "2") (pinfunction "2_2") (pintype "passive"))
      (node (ref "C22") (pin "1") (pinfunction "1_1") (pintype "passive"))
      (node (ref "C24") (pin "2") (pinfunction "2_2") (pintype "passive"))
      (node (ref "C25") (pin "1") (pinfunction "1_1") (pintype "passive"))
      (node (ref "C26") (pin "2") (pinfunction "2_2") (pintype "passive"))
      (node (ref "C27") (pin "1") (pinfunction "1_1") (pintype "passive"))
      (node (ref "C30") (pin "2") (pinfunction "2_2") (pintype "passive"))
      (node (ref "C31") (pin "1") (pinfunction "1_1") (pintype "passive"))
      (node (ref "C33") (pin "2") (pinfunction "2_2") (pintype "passive"))
      (node (ref "C34") (pin "1") (pinfunction "1_1") (pintype "passive"))
      (node (ref "HL1") (pin "1") (pinfunction "1_1") (pintype "passive"))
      (node (ref "R24") (pin "1") (pinfunction "1_1") (pintype "passive"))
      (node (ref "R25") (pin "2") (pinfunction "2_2") (pintype "passive"))
      (node (ref "T1") (pin "9") (pinfunction "9_9") (pintype "passive"))
      (node (ref "XS2") (pin "2") (pinfunction "2_2") (pintype "passive"))
    )
    (net (code "6") (name "Net-(C3-Pad1)") (class "Default")
      (node (ref "C3") (pin "1") (pinfunction "1_1") (pintype "passive"))
      (node (ref "R5") (pin "1") (pinfunction "1_1") (pintype "passive"))
    )
    (net (code "7") (name "Net-(C4-Pad1)") (class "Default")
      (node (ref "C4") (pin "1") (pinfunction "1_1") (pintype "passive"))
      (node (ref "FU1") (pin "2") (pinfunction "2_2") (pintype "passive"))
      (node (ref "L1") (pin "1") (pinfunction "1_1") (pintype "passive"))
      (node (ref "L2") (pin "1") (pinfunction "1_1") (pintype "passive"))
      (node (ref "R7") (pin "2") (pinfunction "2_2") (pintype "passive"))
      (node (ref "RU1") (pin "2") (pinfunction "2_2") (pintype "passive"))
    )
    (net (code "8") (name "Net-(C4-Pad2)") (class "Default")
      (node (ref "C4") (pin "2") (pinfunction "2_2") (pintype "passive"))
      (node (ref "C5") (pin "1") (pinfunction "1_1") (pintype "passive"))
      (node (ref "L5") (pin "1") (pinfunction "1_1") (pintype "passive"))
      (node (ref "R7") (pin "1") (pinfunction "1_1") (pintype "passive"))
      (node (ref "R8") (pin "2") (pinfunction "2_2") (pintype "passive"))
      (node (ref "XS1") (pin "2") (pinfunction "2_2") (pintype "passive"))
    )
    (net (code "9") (name "Net-(C5-Pad2)") (class "Default")
      (node (ref "C5") (pin "2") (pinfunction "2_2") (pintype "passive"))
      (node (ref "K1") (pin "1") (pinfunction "1_1") (pintype "passive"))
      (node (ref "K1") (pin "8") (pinfunction "8_8") (pintype "passive"))
      (node (ref "L1") (pin "2") (pinfunction "2_2") (pintype "passive"))
      (node (ref "L2") (pin "2") (pinfunction "2_2") (pintype "passive"))
      (node (ref "R1") (pin "1") (pinfunction "1_1") (pintype "passive"))
      (node (ref "R2") (pin "1") (pinfunction "1_1") (pintype "passive"))
      (node (ref "R8") (pin "1") (pinfunction "1_1") (pintype "passive"))
      (node (ref "RU1") (pin "1") (pinfunction "1_1") (pintype "passive"))
    )
    (net (code "10") (name "Net-(C7-Pad2)") (class "Default")
      (node (ref "C7") (pin "2") (pinfunction "2_2") (pintype "passive"))
      (node (ref "T1") (pin "4") (pinfunction "4_4") (pintype "passive"))
    )
    (net (code "11") (name "Net-(C8-Pad1)") (class "Default")
      (node (ref "C8") (pin "1") (pinfunction "1_1") (pintype "passive"))
      (node (ref "L2") (pin "3") (pinfunction "3_3") (pintype "passive"))
      (node (ref "L4") (pin "1") (pinfunction "1_1") (pintype "passive"))
    )
    (net (code "12") (name "Net-(C8-Pad2)") (class "Default")
      (node (ref "C8") (pin "2") (pinfunction "2_2") (pintype "passive"))
      (node (ref "L2") (pin "4") (pinfunction "4_4") (pintype "passive"))
      (node (ref "L3") (pin "1") (pinfunction "1_1") (pintype "passive"))
    )
    (net (code "13") (name "Net-(C9-Pad1)") (class "Default")
      (node (ref "C9") (pin "1") (pinfunction "1_1") (pintype "passive"))
      (node (ref "R12") (pin "2") (pinfunction "2_2") (pintype "passive"))
    )
    (net (code "14") (name "Net-(C12-Pad2)") (class "Default")
      (node (ref "C12") (pin "2") (pinfunction "2_2") (pintype "passive"))
      (node (ref "R13") (pin "1") (pinfunction "1_1") (pintype "passive"))
    )
    (net (code "15") (name "Net-(C13-Pad2)") (class "Default")
      (node (ref "C13") (pin "2") (pinfunction "2_2") (pintype "passive"))
      (node (ref "R14") (pin "1") (pinfunction "1_1") (pintype "passive"))
    )
    (net (code "16") (name "Net-(C14-Pad2)") (class "Default")
      (node (ref "C14") (pin "2") (pinfunction "2_2") (pintype "passive"))
      (node (ref "R15") (pin "1") (pinfunction "1_1") (pintype "passive"))
    )
    (net (code "17") (name "Net-(C35-Pad1)") (class "Default")
      (node (ref "C35") (pin "1") (pinfunction "1_1") (pintype "passive"))
      (node (ref "R28") (pin "1") (pinfunction "1_1") (pintype "passive"))
    )
    (net (code "18") (name "Net-(DA1-BP{slash}M)") (class "Default")
      (node (ref "C6") (pin "1") (pinfunction "1_1") (pintype "passive"))
      (node (ref "DA1") (pin "2") (pinfunction "BP/M_2") (pintype "passive"))
    )
    (net (code "19") (name "Net-(DA1-DRAIN)") (class "Default")
      (node (ref "DA1") (pin "4") (pinfunction "DRAIN_4") (pintype "passive"))
      (node (ref "T1") (pin "3") (pinfunction "3_3") (pintype "passive"))
      (node (ref "VD4") (pin "2") (pinfunction "A_2") (pintype "passive"))
    )
    (net (code "20") (name "Net-(DA1-EN{slash}UV)") (class "Default")
      (node (ref "DA1") (pin "1") (pinfunction "EN/UV_1") (pintype "input"))
      (node (ref "R10") (pin "1") (pinfunction "1_1") (pintype "passive"))
    )
    (net (code "21") (name "Net-(DA2-ADJ)") (class "Default")
      (node (ref "C26") (pin "1") (pinfunction "1_1") (pintype "passive"))
      (node (ref "DA2") (pin "1") (pinfunction "ADJ_1") (pintype "input"))
      (node (ref "R24") (pin "2") (pinfunction "2_2") (pintype "passive"))
      (node (ref "R26") (pin "2") (pinfunction "2_2") (pintype "passive"))
    )
    (net (code "22") (name "Net-(DA2-VIN)") (class "Default")
      (node (ref "C21") (pin "1") (pinfunction "1_1") (pintype "passive"))
      (node (ref "C24") (pin "1") (pinfunction "1_1") (pintype "passive"))
      (node (ref "DA2") (pin "3") (pinfunction "VIN_3") (pintype "power_in"))
      (node (ref "L6") (pin "2") (pinfunction "2_2") (pintype "passive"))
    )
    (net (code "23") (name "Net-(DA3-ADJ)") (class "Default")
      (node (ref "C27") (pin "2") (pinfunction "2_2") (pintype "passive"))
      (node (ref "DA3") (pin "1") (pinfunction "ADJ_1") (pintype "input"))
      (node (ref "R25") (pin "1") (pinfunction "1_1") (pintype "passive"))
      (node (ref "R27") (pin "2") (pinfunction "2_2") (pintype "passive"))
    )
    (net (code "24") (name "Net-(DA3-VIN)") (class "Default")
      (node (ref "C22") (pin "2") (pinfunction "2_2") (pintype "passive"))
      (node (ref "C25") (pin "2") (pinfunction "2_2") (pintype "passive"))
      (node (ref "DA3") (pin "2") (pinfunction "VIN_2") (pintype "power_in"))
      (node (ref "L7") (pin "2") (pinfunction "2_2") (pintype "passive"))
    )
    (net (code "25") (name "Net-(DA4-FREQ)") (class "Default")
      (node (ref "DA4") (pin "4") (pinfunction "FREQ_4") (pintype "passive"))
      (node (ref "R21") (pin "1") (pinfunction "1_1") (pintype "passive"))
    )
    (net (code "26") (name "Net-(DA4-GATE)") (class "Default")
      (node (ref "DA4") (pin "8") (pinfunction "GATE_8") (pintype "passive"))
      (node (ref "R22") (pin "1") (pinfunction "1_1") (pintype "passive"))
    )
    (net (code "27") (name "Net-(DA4-ICOMP)") (class "Default")
      (node (ref "C23") (pin "2") (pinfunction "2_2") (pintype "passive"))
      (node (ref "DA4") (pin "2") (pinfunction "ICOMP_2") (pintype "passive"))
    )
    (net (code "28") (name "Net-(DA4-ISEN)") (class "Default")
      (node (ref "DA4") (pin "3") (pinfunction "ISEN_3") (pintype "passive"))
      (node (ref "R19") (pin "1") (pinfunction "1_1") (pintype "passive"))
    )
    (net (code "29") (name "Net-(DA4-VCOMP)") (class "Default")
      (node (ref "C32") (pin "1") (pinfunction "1_1") (pintype "passive"))
      (node (ref "DA4") (pin "5") (pinfunction "VCOMP_5") (pintype "passive"))
      (node (ref "R28") (pin "2") (pinfunction "2_2") (pintype "passive"))
    )
    (net (code "30") (name "Net-(DA4-VSEN)") (class "Default")
      (node (ref "C36") (pin "1") (pinfunction "1_1") (pintype "passive"))
      (node (ref "DA4") (pin "6") (pinfunction "VSEN_6") (pintype "passive"))
      (node (ref "R31") (pin "1") (pinfunction "1_1") (pintype "passive"))
      (node (ref "R32") (pin "1") (pinfunction "1_1") (pintype "passive"))
      (node (ref "R33") (pin "2") (pinfunction "2_2") (pintype "passive"))
    )
    (net (code "31") (name "Net-(FU1-Pad1)") (class "Default")
      (node (ref "FU1") (pin "1") (pinfunction "1_1") (pintype "passive"))
      (node (ref "XS1") (pin "1") (pinfunction "1_1") (pintype "passive"))
    )
    (net (code "32") (name "Net-(HL1-Pad2)") (class "Default")
      (node (ref "HL1") (pin "2") (pinfunction "2_2") (pintype "passive"))
      (node (ref "R29") (pin "1") (pinfunction "1_1") (pintype "passive"))
    )
    (net (code "33") (name "Net-(K1-Pad2)") (class "Default")
      (node (ref "K1") (pin "2") (pinfunction "2_2") (pintype "passive"))
      (node (ref "K1") (pin "7") (pinfunction "7_7") (pintype "passive"))
      (node (ref "R1") (pin "2") (pinfunction "2_2") (pintype "passive"))
      (node (ref "R2") (pin "2") (pinfunction "2_2") (pintype "passive"))
      (node (ref "XS1") (pin "3") (pinfunction "3_3") (pintype "passive"))
    )
    (net (code "34") (name "Net-(R30-Pad1)") (class "Default")
      (node (ref "R30") (pin "1") (pinfunction "1_1") (pintype "passive"))
      (node (ref "R31") (pin "2") (pinfunction "2_2") (pintype "passive"))
    )
    (net (code "35") (name "Net-(VD1-A)") (class "Default")
      (node (ref "K1") (pin "5") (pinfunction "5_5") (pintype "passive"))
      (node (ref "VD1") (pin "2") (pinfunction "A_2") (pintype "passive"))
      (node (ref "VT1") (pin "2") (pinfunction "C_2") (pintype "passive"))
    )
    (net (code "36") (name "Net-(VD2-AC1)") (class "Default")
      (node (ref "C2") (pin "2") (pinfunction "2_2") (pintype "passive"))
      (node (ref "L1") (pin "3") (pinfunction "3_3") (pintype "passive"))
      (node (ref "VD2") (pin "2") (pinfunction "AC1_2") (pintype "passive"))
    )
    (net (code "37") (name "Net-(VD2-AC2)") (class "Default")
      (node (ref "C2") (pin "1") (pinfunction "1_1") (pintype "passive"))
      (node (ref "L1") (pin "4") (pinfunction "4_4") (pintype "passive"))
      (node (ref "VD2") (pin "3") (pinfunction "AC2_3") (pintype "passive"))
    )
    (net (code "38") (name "Net-(VD3-ANODE)") (class "Default")
      (node (ref "R4") (pin "2") (pinfunction "2_2") (pintype "passive"))
      (node (ref "VD3") (pin "2") (pinfunction "ANODE_2") (pintype "power_in"))
      (node (ref "VT1") (pin "1") (pinfunction "B_1") (pintype "passive"))
    )
    (net (code "39") (name "Net-(VD3-CATHODE)") (class "Default")
      (node (ref "R3") (pin "1") (pinfunction "1_1") (pintype "passive"))
      (node (ref "VD3") (pin "1") (pinfunction "CATHODE_1") (pintype "passive"))
    )
    (net (code "40") (name "Net-(VD4-C)") (class "Default")
      (node (ref "R6") (pin "2") (pinfunction "2_2") (pintype "passive"))
      (node (ref "VD4") (pin "1") (pinfunction "C_1") (pintype "passive"))
    )
    (net (code "41") (name "Net-(VD5-C)") (class "Default")
      (node (ref "R5") (pin "2") (pinfunction "2_2") (pintype "passive"))
      (node (ref "R6") (pin "1") (pinfunction "1_1") (pintype "passive"))
      (node (ref "R9") (pin "1") (pinfunction "1_1") (pintype "passive"))
      (node (ref "VD5") (pin "1") (pinfunction "C_1") (pintype "passive"))
    )
    (net (code "42") (name "Net-(VD6-A)") (class "Default")
      (node (ref "R13") (pin "2") (pinfunction "2_2") (pintype "passive"))
      (node (ref "T1") (pin "10") (pinfunction "10_10") (pintype "passive"))
      (node (ref "VD6") (pin "2") (pinfunction "A_2") (pintype "passive"))
    )
    (net (code "43") (name "Net-(VD6-C)") (class "Default")
      (node (ref "C12") (pin "1") (pinfunction "1_1") (pintype "passive"))
      (node (ref "C16") (pin "1") (pinfunction "1_1") (pintype "passive"))
      (node (ref "L6") (pin "1") (pinfunction "1_1") (pintype "passive"))
      (node (ref "VD6") (pin "1") (pinfunction "C_1") (pintype "passive"))
    )
    (net (code "44") (name "Net-(VD7-A)") (class "Default")
      (node (ref "C13") (pin "1") (pinfunction "1_1") (pintype "passive"))
      (node (ref "C17") (pin "2") (pinfunction "2_2") (pintype "passive"))
      (node (ref "L7") (pin "1") (pinfunction "1_1") (pintype "passive"))
      (node (ref "VD7") (pin "2") (pinfunction "A_2") (pintype "passive"))
    )
    (net (code "45") (name "Net-(VD7-C)") (class "Default")
      (node (ref "R14") (pin "2") (pinfunction "2_2") (pintype "passive"))
      (node (ref "T1") (pin "8") (pinfunction "8_8") (pintype "passive"))
      (node (ref "VD7") (pin "1") (pinfunction "C_1") (pintype "passive"))
    )
    (net (code "46") (name "Net-(VD8-A)") (class "Default")
      (node (ref "R15") (pin "2") (pinfunction "2_2") (pintype "passive"))
      (node (ref "T1") (pin "5") (pinfunction "5_5") (pintype "passive"))
      (node (ref "VD8") (pin "2") (pinfunction "A_2") (pintype "passive"))
    )
    (net (code "47") (name "Net-(VD9-ANODE)") (class "Default")
      (node (ref "R11") (pin "1") (pinfunction "1_1") (pintype "passive"))
      (node (ref "R18") (pin "1") (pinfunction "1_1") (pintype "passive"))
      (node (ref "VD9") (pin "2") (pinfunction "ANODE_2") (pintype "power_in"))
    )
    (net (code "48") (name "Net-(VD10-M)") (class "Default")
      (node (ref "C20") (pin "1") (pinfunction "1_1") (pintype "passive"))
      (node (ref "R19") (pin "2") (pinfunction "2_2") (pintype "passive"))
      (node (ref "R20") (pin "1") (pinfunction "1_1") (pintype "passive"))
      (node (ref "VD10") (pin "1") (pinfunction "M_1") (pintype "passive"))
    )
    (net (code "49") (name "Net-(VD10-P)") (class "Default")
      (node (ref "C20") (pin "2") (pinfunction "2_2") (pintype "passive"))
      (node (ref "L8") (pin "1") (pinfunction "1_1") (pintype "passive"))
      (node (ref "VD10") (pin "4") (pinfunction "P_4") (pintype "passive"))
      (node (ref "VD11") (pin "1") (pinfunction "A1_1") (pintype "passive"))
    )
    (net (code "50") (name "Net-(VD11-A2)") (class "Default")
      (node (ref "L8") (pin "2") (pinfunction "2_2") (pintype "passive"))
      (node (ref "VD11") (pin "3") (pinfunction "A2_3") (pintype "passive"))
      (node (ref "VT3") (pin "2") (pinfunction "D_2") (pintype "passive"))
    )
    (net (code "51") (name "Net-(VT2-B)") (class "Default")
      (node (ref "R11") (pin "2") (pinfunction "2_2") (pintype "passive"))
      (node (ref "R12") (pin "1") (pinfunction "1_1") (pintype "passive"))
      (node (ref "VT2") (pin "1") (pinfunction "B_1") (pintype "passive"))
    )
    (net (code "52") (name "Net-(VT2-C)") (class "Default")
      (node (ref "R10") (pin "2") (pinfunction "2_2") (pintype "passive"))
      (node (ref "VT2") (pin "2") (pinfunction "C_2") (pintype "passive"))
    )
    (net (code "53") (name "Net-(VT3-G)") (class "Default")
      (node (ref "R22") (pin "2") (pinfunction "2_2") (pintype "passive"))
      (node (ref "R23") (pin "2") (pinfunction "2_2") (pintype "passive"))
      (node (ref "VT3") (pin "1") (pinfunction "G_1") (pintype "passive"))
    )
    (net (code "54") (name "PGND") (class "Default")
      (node (ref "C1") (pin "2") (pinfunction "2_2") (pintype "passive"))
      (node (ref "C18") (pin "2") (pinfunction "2_2") (pintype "passive"))
      (node (ref "C19") (pin "2") (pinfunction "2_2") (pintype "passive"))
      (node (ref "C23") (pin "1") (pinfunction "1_1") (pintype "passive"))
      (node (ref "C28") (pin "2") (pinfunction "2_2") (pintype "passive"))
      (node (ref "C29") (pin "2") (pinfunction "2_2") (pintype "passive"))
      (node (ref "C32") (pin "2") (pinfunction "2_2") (pintype "passive"))
      (node (ref "C35") (pin "2") (pinfunction "2_2") (pintype "passive"))
      (node (ref "C36") (pin "2") (pinfunction "2_2") (pintype "passive"))
      (node (ref "C6") (pin "2") (pinfunction "2_2") (pintype "passive"))
      (node (ref "C7") (pin "1") (pinfunction "1_1") (pintype "passive"))
      (node (ref "C9") (pin "2") (pinfunction "2_2") (pintype "passive"))
      (node (ref "DA1") (pin "5") (pinfunction "SOURCE_5") (pintype "passive"))
      (node (ref "DA1") (pin "6") (pinfunction "SOURCE_6") (pintype "passive"))
      (node (ref "DA1") (pin "7") (pinfunction "SOURCE_7") (pintype "passive"))
      (node (ref "DA1") (pin "8") (pinfunction "SOURCE_8") (pintype "passive"))
      (node (ref "DA4") (pin "1") (pinfunction "GND_1") (pintype "passive"))
      (node (ref "R18") (pin "2") (pinfunction "2_2") (pintype "passive"))
      (node (ref "R20") (pin "2") (pinfunction "2_2") (pintype "passive"))
      (node (ref "R21") (pin "2") (pinfunction "2_2") (pintype "passive"))
      (node (ref "R23") (pin "1") (pinfunction "1_1") (pintype "passive"))
      (node (ref "R32") (pin "2") (pinfunction "2_2") (pintype "passive"))
      (node (ref "R33") (pin "1") (pinfunction "1_1") (pintype "passive"))
      (node (ref "R4") (pin "1") (pinfunction "1_1") (pintype "passive"))
      (node (ref "T1") (pin "6") (pinfunction "6_6") (pintype "passive"))
      (node (ref "VD2") (pin "4") (pinfunction "P_4") (pintype "passive"))
      (node (ref "VT1") (pin "3") (pinfunction "E_3") (pintype "passive"))
      (node (ref "VT2") (pin "3") (pinfunction "E_3") (pintype "passive"))
      (node (ref "VT3") (pin "3") (pinfunction "S_3") (pintype "passive"))
    )
    (net (code "55") (name "VCC_380V") (class "Default")
      (node (ref "C29") (pin "1") (pinfunction "1_1") (pintype "passive"))
      (node (ref "R30") (pin "2") (pinfunction "2_2") (pintype "passive"))
      (node (ref "VD11") (pin "2") (pinfunction "C_2") (pintype "passive"))
    )
    (net (code "56") (name "VCC_NONISO_12V0P") (class "Default")
      (node (ref "C14") (pin "1") (pinfunction "1_1") (pintype "passive"))
      (node (ref "C18") (pin "1") (pinfunction "1_1") (pintype "passive"))
      (node (ref "C19") (pin "1") (pinfunction "1_1") (pintype "passive"))
      (node (ref "C28") (pin "1") (pinfunction "1_1") (pintype "passive"))
      (node (ref "DA4") (pin "7") (pinfunction "VCC_7") (pintype "passive"))
      (node (ref "K1") (pin "4") (pinfunction "4_4") (pintype "passive"))
      (node (ref "R3") (pin "2") (pinfunction "2_2") (pintype "passive"))
      (node (ref "VD1") (pin "1") (pinfunction "C_1") (pintype "passive"))
      (node (ref "VD8") (pin "1") (pinfunction "C_1") (pintype "passive"))
      (node (ref "VD9") (pin "1") (pinfunction "CATHODE_1") (pintype "passive"))
    )
    (net (code "57") (name "VCC_STANDBY_12V0N") (class "Default")
      (node (ref "C31") (pin "2") (pinfunction "2_2") (pintype "passive"))
      (node (ref "C34") (pin "2") (pinfunction "2_2") (pintype "passive"))
      (node (ref "DA3") (pin "3") (pinfunction "VOUT_3") (pintype "power_in"))
      (node (ref "R27") (pin "1") (pinfunction "1_1") (pintype "passive"))
      (node (ref "XS2") (pin "3") (pinfunction "3_3") (pintype "passive"))
    )
    (net (code "58") (name "VCC_STANDBY_12V0P") (class "Default")
      (node (ref "C30") (pin "1") (pinfunction "1_1") (pintype "passive"))
      (node (ref "C33") (pin "1") (pinfunction "1_1") (pintype "passive"))
      (node (ref "DA2") (pin "2") (pinfunction "VOUT_2") (pintype "power_in"))
      (node (ref "R26") (pin "1") (pinfunction "1_1") (pintype "passive"))
      (node (ref "R29") (pin "2") (pinfunction "2_2") (pintype "passive"))
      (node (ref "XS2") (pin "1") (pinfunction "1_1") (pintype "passive"))
    )
    (net (code "59") (name "unconnected-(K1-Pad3)") (class "Default")
      (node (ref "K1") (pin "3") (pinfunction "3_3") (pintype "passive+no_connect"))
    )
    (net (code "60") (name "unconnected-(K1-Pad6)") (class "Default")
      (node (ref "K1") (pin "6") (pinfunction "6_6") (pintype "passive+no_connect"))
    )
  )
)
